# 1107.net
KiCad netlist of a schematic drawn in EAGLE
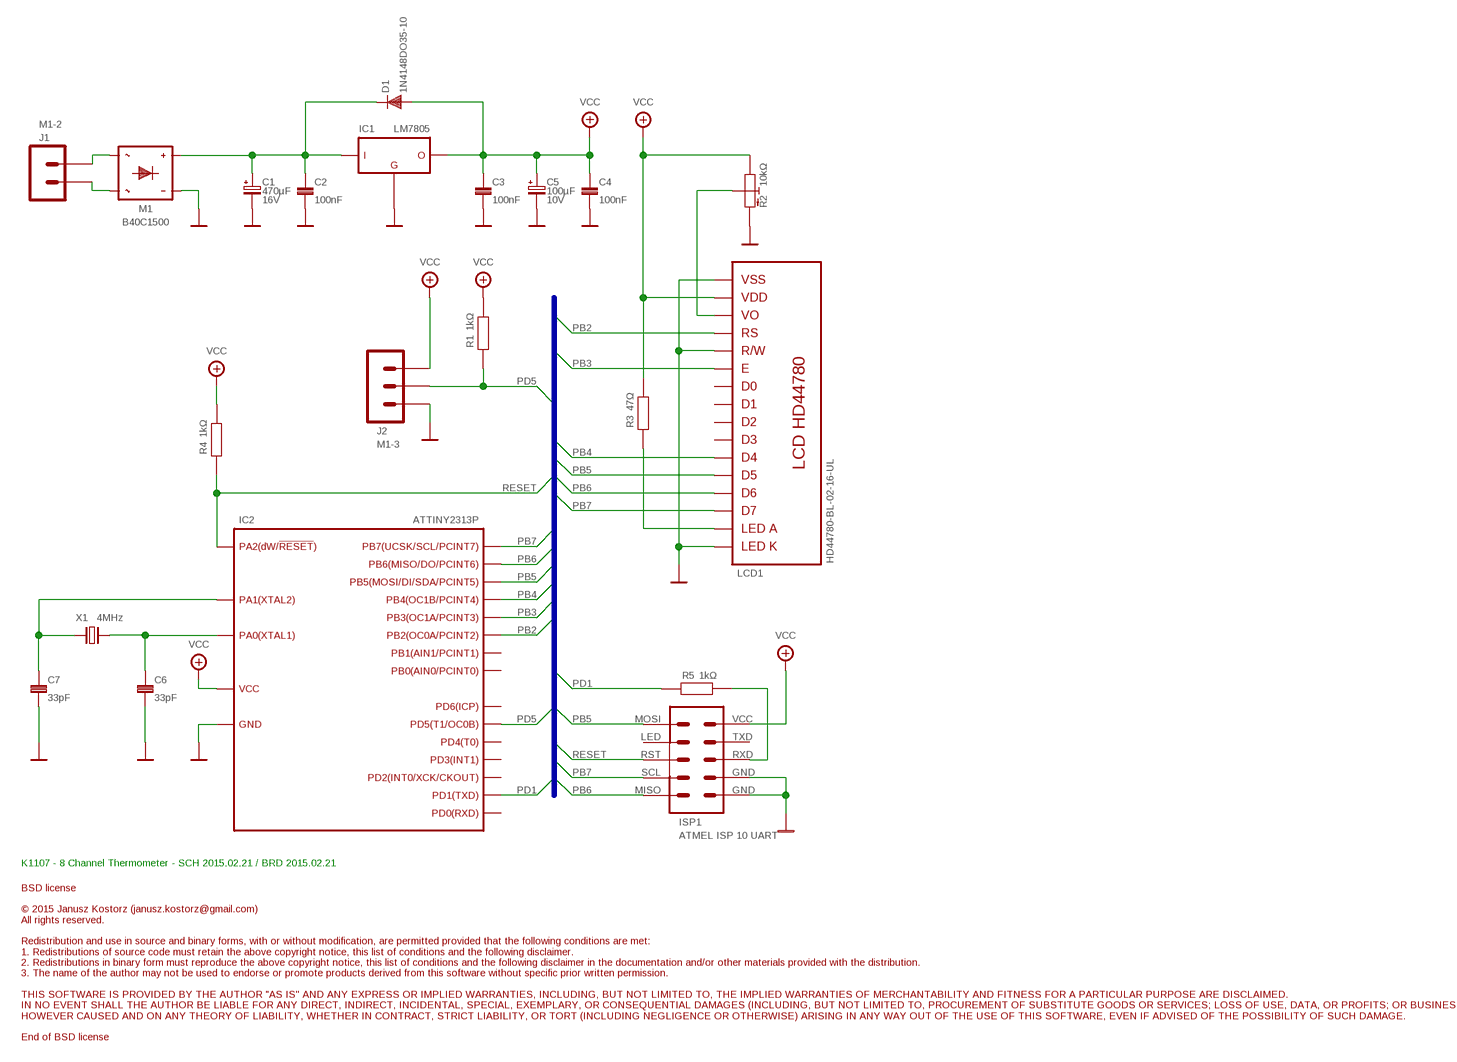
[diagram p0: schematic, sheet 1]

(export (version "E")
  (design (tool "Eeschema 10.0.6"))
  (components
    (comp (ref "C1")
      (value "470µF")
      (footprint "eagle-import:E-080-150-035-060")
      (fields (field (name "VOLTAGE") "16V"))
      (libsource (lib "eagle-import") (part "FC1C471L"))
    )
    (comp (ref "C2")
      (value "100nF")
      (footprint "eagle-import:C1206")
      (libsource (lib "eagle-import") (part "CC1206"))
    )
    (comp (ref "C3")
      (value "100nF")
      (footprint "eagle-import:C1206")
      (libsource (lib "eagle-import") (part "CC1206"))
    )
    (comp (ref "C4")
      (value "100nF")
      (footprint "eagle-import:C1206")
      (libsource (lib "eagle-import") (part "CC1206"))
    )
    (comp (ref "C5")
      (value "100µF")
      (footprint "eagle-import:E-050-150-020-050")
      (fields (field (name "VOLTAGE") "10V"))
      (libsource (lib "eagle-import") (part "FC1A101"))
    )
    (comp (ref "C6")
      (value "33pF")
      (footprint "eagle-import:C1206")
      (libsource (lib "eagle-import") (part "CC1206"))
    )
    (comp (ref "C7")
      (value "33pF")
      (footprint "eagle-import:C1206")
      (libsource (lib "eagle-import") (part "CC1206"))
    )
    (comp (ref "D1")
      (value "1N4148DO35-10")
      (footprint "eagle-import:DO35-10")
      (libsource (lib "eagle-import") (part "1N4148DO35-10"))
    )
    (comp (ref "IC1")
      (value "LM7805")
      (footprint "eagle-import:TO220-H")
      (libsource (lib "eagle-import") (part "LM78XX-C-H"))
    )
    (comp (ref "IC2")
      (value "ATTINY2313P")
      (footprint "eagle-import:DIL20")
      (libsource (lib "eagle-import") (part "ATTINY2313P"))
    )
    (comp (ref "ISP1")
      (value "ATMEL ISP 10 UART")
      (footprint "eagle-import:MM-10-V")
      (libsource (lib "eagle-import") (part "ATMEL-ISP-10-UART-V"))
    )
    (comp (ref "J1")
      (value "M1-2")
      (footprint "eagle-import:1-2")
      (libsource (lib "eagle-import") (part "1-2"))
    )
    (comp (ref "J2")
      (value "M1-3")
      (footprint "eagle-import:1-3")
      (libsource (lib "eagle-import") (part "1-3"))
    )
    (comp (ref "LCD1")
      (value "HD44780-BL-02-16-UL")
      (footprint "eagle-import:02-16-UL-BL")
      (libsource (lib "eagle-import") (part "HD44780-BL-02-16-UL"))
    )
    (comp (ref "M1")
      (value "B40C1500")
      (footprint "eagle-import:RB1A")
      (libsource (lib "eagle-import") (part "B40C1500R"))
    )
    (comp (ref "R1")
      (value "1kΩ")
      (footprint "eagle-import:M1206")
      (libsource (lib "eagle-import") (part "RM1206"))
    )
    (comp (ref "R2")
      (value "10kΩ")
      (footprint "eagle-import:POT_CA6V")
      (libsource (lib "eagle-import") (part "POTCA6V"))
    )
    (comp (ref "R3")
      (value "47Ω")
      (footprint "eagle-import:M1206")
      (libsource (lib "eagle-import") (part "RM1206"))
    )
    (comp (ref "R4")
      (value "1kΩ")
      (footprint "eagle-import:M1206")
      (libsource (lib "eagle-import") (part "RM1206"))
    )
    (comp (ref "R5")
      (value "1kΩ")
      (footprint "eagle-import:M1206")
      (libsource (lib "eagle-import") (part "RM1206"))
    )
    (comp (ref "X1")
      (value "4MHz")
      (footprint "eagle-import:HC49_S")
      (libsource (lib "eagle-import") (part "CRYSTALHC49S"))
    )
  )
  (nets
    (net (code "1") (name "/PB2") (class "Default")
      (node (ref "IC2") (pin "14") (pinfunction "PB2_14") (pintype "bidirectional"))
      (node (ref "LCD1") (pin "4") (pinfunction "RS_4") (pintype "input"))
    )
    (net (code "2") (name "/PB3") (class "Default")
      (node (ref "IC2") (pin "15") (pinfunction "PB3_15") (pintype "bidirectional"))
      (node (ref "LCD1") (pin "6") (pinfunction "E_6") (pintype "input"))
    )
    (net (code "3") (name "/PB4") (class "Default")
      (node (ref "IC2") (pin "16") (pinfunction "PB4_16") (pintype "bidirectional"))
      (node (ref "LCD1") (pin "11") (pinfunction "DB4_11") (pintype "bidirectional"))
    )
    (net (code "4") (name "/PB5") (class "Default")
      (node (ref "IC2") (pin "17") (pinfunction "PB5_17") (pintype "bidirectional"))
      (node (ref "ISP1") (pin "1") (pinfunction "MOSI_1") (pintype "bidirectional"))
      (node (ref "LCD1") (pin "12") (pinfunction "DB5_12") (pintype "bidirectional"))
    )
    (net (code "5") (name "/PB6") (class "Default")
      (node (ref "IC2") (pin "18") (pinfunction "PB6_18") (pintype "bidirectional"))
      (node (ref "ISP1") (pin "9") (pinfunction "MISO_9") (pintype "bidirectional"))
      (node (ref "LCD1") (pin "13") (pinfunction "DB6_13") (pintype "bidirectional"))
    )
    (net (code "6") (name "/PB7") (class "Default")
      (node (ref "IC2") (pin "19") (pinfunction "PB7_19") (pintype "bidirectional"))
      (node (ref "ISP1") (pin "7") (pinfunction "SCL_7") (pintype "bidirectional"))
      (node (ref "LCD1") (pin "14") (pinfunction "DB7_14") (pintype "bidirectional"))
    )
    (net (code "7") (name "/PD1") (class "Default")
      (node (ref "IC2") (pin "3") (pinfunction "PD1_3") (pintype "bidirectional"))
      (node (ref "R5") (pin "1") (pinfunction "1_1") (pintype "passive"))
    )
    (net (code "8") (name "/PD5") (class "Default")
      (node (ref "IC2") (pin "9") (pinfunction "PD5_9") (pintype "bidirectional"))
      (node (ref "J2") (pin "2") (pinfunction "2_2") (pintype "passive"))
      (node (ref "R1") (pin "1") (pinfunction "1_1") (pintype "passive"))
    )
    (net (code "9") (name "/RESET") (class "Default")
      (node (ref "IC2") (pin "1") (pinfunction "PA2_1") (pintype "bidirectional"))
      (node (ref "ISP1") (pin "5") (pinfunction "RST_5") (pintype "bidirectional"))
      (node (ref "R4") (pin "1") (pinfunction "1_1") (pintype "passive"))
    )
    (net (code "10") (name "GND") (class "Default")
      (node (ref "C1") (pin "-") (pinfunction "-_-") (pintype "passive"))
      (node (ref "C2") (pin "2") (pinfunction "2_2") (pintype "passive"))
      (node (ref "C3") (pin "2") (pinfunction "2_2") (pintype "passive"))
      (node (ref "C4") (pin "2") (pinfunction "2_2") (pintype "passive"))
      (node (ref "C5") (pin "-") (pinfunction "-_-") (pintype "passive"))
      (node (ref "C6") (pin "2") (pinfunction "2_2") (pintype "passive"))
      (node (ref "C7") (pin "2") (pinfunction "2_2") (pintype "passive"))
      (node (ref "IC1") (pin "2") (pinfunction "GND_2") (pintype "passive"))
      (node (ref "IC2") (pin "10") (pinfunction "GND_10") (pintype "power_in"))
      (node (ref "ISP1") (pin "10") (pinfunction "GND_10") (pintype "power_in"))
      (node (ref "ISP1") (pin "8") (pinfunction "GND_8") (pintype "power_in"))
      (node (ref "J2") (pin "3") (pinfunction "3_3") (pintype "passive"))
      (node (ref "LCD1") (pin "1") (pinfunction "VSS_1") (pintype "power_in"))
      (node (ref "LCD1") (pin "16") (pinfunction "K_16") (pintype "power_in"))
      (node (ref "LCD1") (pin "5") (pinfunction "R/W_5") (pintype "input"))
      (node (ref "M1") (pin "-") (pinfunction "-_-") (pintype "passive"))
      (node (ref "R2") (pin "E") (pinfunction "E_E") (pintype "passive"))
    )
    (net (code "11") (name "Net-(IC1-IN)") (class "Default")
      (node (ref "C1") (pin "+") (pinfunction "+_+") (pintype "passive"))
      (node (ref "C2") (pin "1") (pinfunction "1_1") (pintype "passive"))
      (node (ref "D1") (pin "C") (pinfunction "C_C") (pintype "passive"))
      (node (ref "IC1") (pin "1") (pinfunction "IN_1") (pintype "input"))
      (node (ref "M1") (pin "+") (pinfunction "+_+") (pintype "passive"))
    )
    (net (code "12") (name "Net-(IC2-PA0)") (class "Default")
      (node (ref "C6") (pin "1") (pinfunction "1_1") (pintype "passive"))
      (node (ref "IC2") (pin "5") (pinfunction "PA0_5") (pintype "bidirectional"))
      (node (ref "X1") (pin "2") (pinfunction "2_2") (pintype "passive"))
    )
    (net (code "13") (name "Net-(IC2-PA1)") (class "Default")
      (node (ref "C7") (pin "1") (pinfunction "1_1") (pintype "passive"))
      (node (ref "IC2") (pin "4") (pinfunction "PA1_4") (pintype "bidirectional"))
      (node (ref "X1") (pin "1") (pinfunction "1_1") (pintype "passive"))
    )
    (net (code "14") (name "Net-(ISP1-RXD)") (class "Default")
      (node (ref "ISP1") (pin "6") (pinfunction "RXD_6") (pintype "bidirectional"))
      (node (ref "R5") (pin "2") (pinfunction "2_2") (pintype "passive"))
    )
    (net (code "15") (name "Net-(J1-Pad1)") (class "Default")
      (node (ref "J1") (pin "1") (pinfunction "1_1") (pintype "passive"))
      (node (ref "M1") (pin "AC@2") (pinfunction "~_AC@2") (pintype "passive"))
    )
    (net (code "16") (name "Net-(J1-Pad2)") (class "Default")
      (node (ref "J1") (pin "2") (pinfunction "2_2") (pintype "passive"))
      (node (ref "M1") (pin "AC@1") (pinfunction "~_AC@1") (pintype "passive"))
    )
    (net (code "17") (name "Net-(LCD1-A)") (class "Default")
      (node (ref "LCD1") (pin "15") (pinfunction "A_15") (pintype "power_in"))
      (node (ref "R3") (pin "1") (pinfunction "1_1") (pintype "passive"))
    )
    (net (code "18") (name "Net-(LCD1-VO)") (class "Default")
      (node (ref "LCD1") (pin "3") (pinfunction "VO_3") (pintype "bidirectional"))
      (node (ref "R2") (pin "S") (pinfunction "S_S") (pintype "passive"))
    )
    (net (code "19") (name "VCC") (class "Default")
      (node (ref "C3") (pin "1") (pinfunction "1_1") (pintype "passive"))
      (node (ref "C4") (pin "1") (pinfunction "1_1") (pintype "passive"))
      (node (ref "C5") (pin "+") (pinfunction "+_+") (pintype "passive"))
      (node (ref "D1") (pin "A") (pinfunction "A_A") (pintype "passive"))
      (node (ref "IC1") (pin "3") (pinfunction "OUT_3") (pintype "passive"))
      (node (ref "IC2") (pin "20") (pinfunction "VCC_20") (pintype "power_in"))
      (node (ref "ISP1") (pin "2") (pinfunction "VCC_2") (pintype "power_in"))
      (node (ref "J2") (pin "1") (pinfunction "1_1") (pintype "passive"))
      (node (ref "LCD1") (pin "2") (pinfunction "VDD_2") (pintype "power_in"))
      (node (ref "R1") (pin "2") (pinfunction "2_2") (pintype "passive"))
      (node (ref "R2") (pin "A") (pinfunction "A_A") (pintype "passive"))
      (node (ref "R3") (pin "2") (pinfunction "2_2") (pintype "passive"))
      (node (ref "R4") (pin "2") (pinfunction "2_2") (pintype "passive"))
    )
    (net (code "20") (name "unconnected-(IC2-PB0-Pad12)") (class "Default")
      (node (ref "IC2") (pin "12") (pinfunction "PB0_12") (pintype "bidirectional"))
    )
    (net (code "21") (name "unconnected-(IC2-PB1-Pad13)") (class "Default")
      (node (ref "IC2") (pin "13") (pinfunction "PB1_13") (pintype "bidirectional"))
    )
    (net (code "22") (name "unconnected-(IC2-PD0-Pad2)") (class "Default")
      (node (ref "IC2") (pin "2") (pinfunction "PD0_2") (pintype "bidirectional"))
    )
    (net (code "23") (name "unconnected-(IC2-PD2-Pad6)") (class "Default")
      (node (ref "IC2") (pin "6") (pinfunction "PD2_6") (pintype "bidirectional"))
    )
    (net (code "24") (name "unconnected-(IC2-PD3-Pad7)") (class "Default")
      (node (ref "IC2") (pin "7") (pinfunction "PD3_7") (pintype "bidirectional"))
    )
    (net (code "25") (name "unconnected-(IC2-PD4-Pad8)") (class "Default")
      (node (ref "IC2") (pin "8") (pinfunction "PD4_8") (pintype "bidirectional"))
    )
    (net (code "26") (name "unconnected-(IC2-PD6-Pad11)") (class "Default")
      (node (ref "IC2") (pin "11") (pinfunction "PD6_11") (pintype "bidirectional"))
    )
    (net (code "27") (name "unconnected-(ISP1-LED-Pad3)") (class "Default")
      (node (ref "ISP1") (pin "3") (pinfunction "LED_3") (pintype "bidirectional"))
    )
    (net (code "28") (name "unconnected-(ISP1-TXD-Pad4)") (class "Default")
      (node (ref "ISP1") (pin "4") (pinfunction "TXD_4") (pintype "bidirectional"))
    )
    (net (code "29") (name "unconnected-(LCD1-DB0-Pad7)") (class "Default")
      (node (ref "LCD1") (pin "7") (pinfunction "DB0_7") (pintype "bidirectional"))
    )
    (net (code "30") (name "unconnected-(LCD1-DB1-Pad8)") (class "Default")
      (node (ref "LCD1") (pin "8") (pinfunction "DB1_8") (pintype "bidirectional"))
    )
    (net (code "31") (name "unconnected-(LCD1-DB2-Pad9)") (class "Default")
      (node (ref "LCD1") (pin "9") (pinfunction "DB2_9") (pintype "bidirectional"))
    )
    (net (code "32") (name "unconnected-(LCD1-DB3-Pad10)") (class "Default")
      (node (ref "LCD1") (pin "10") (pinfunction "DB3_10") (pintype "bidirectional"))
    )
  )
)
